# shield.net
KiCad netlist of a schematic drawn in EAGLE
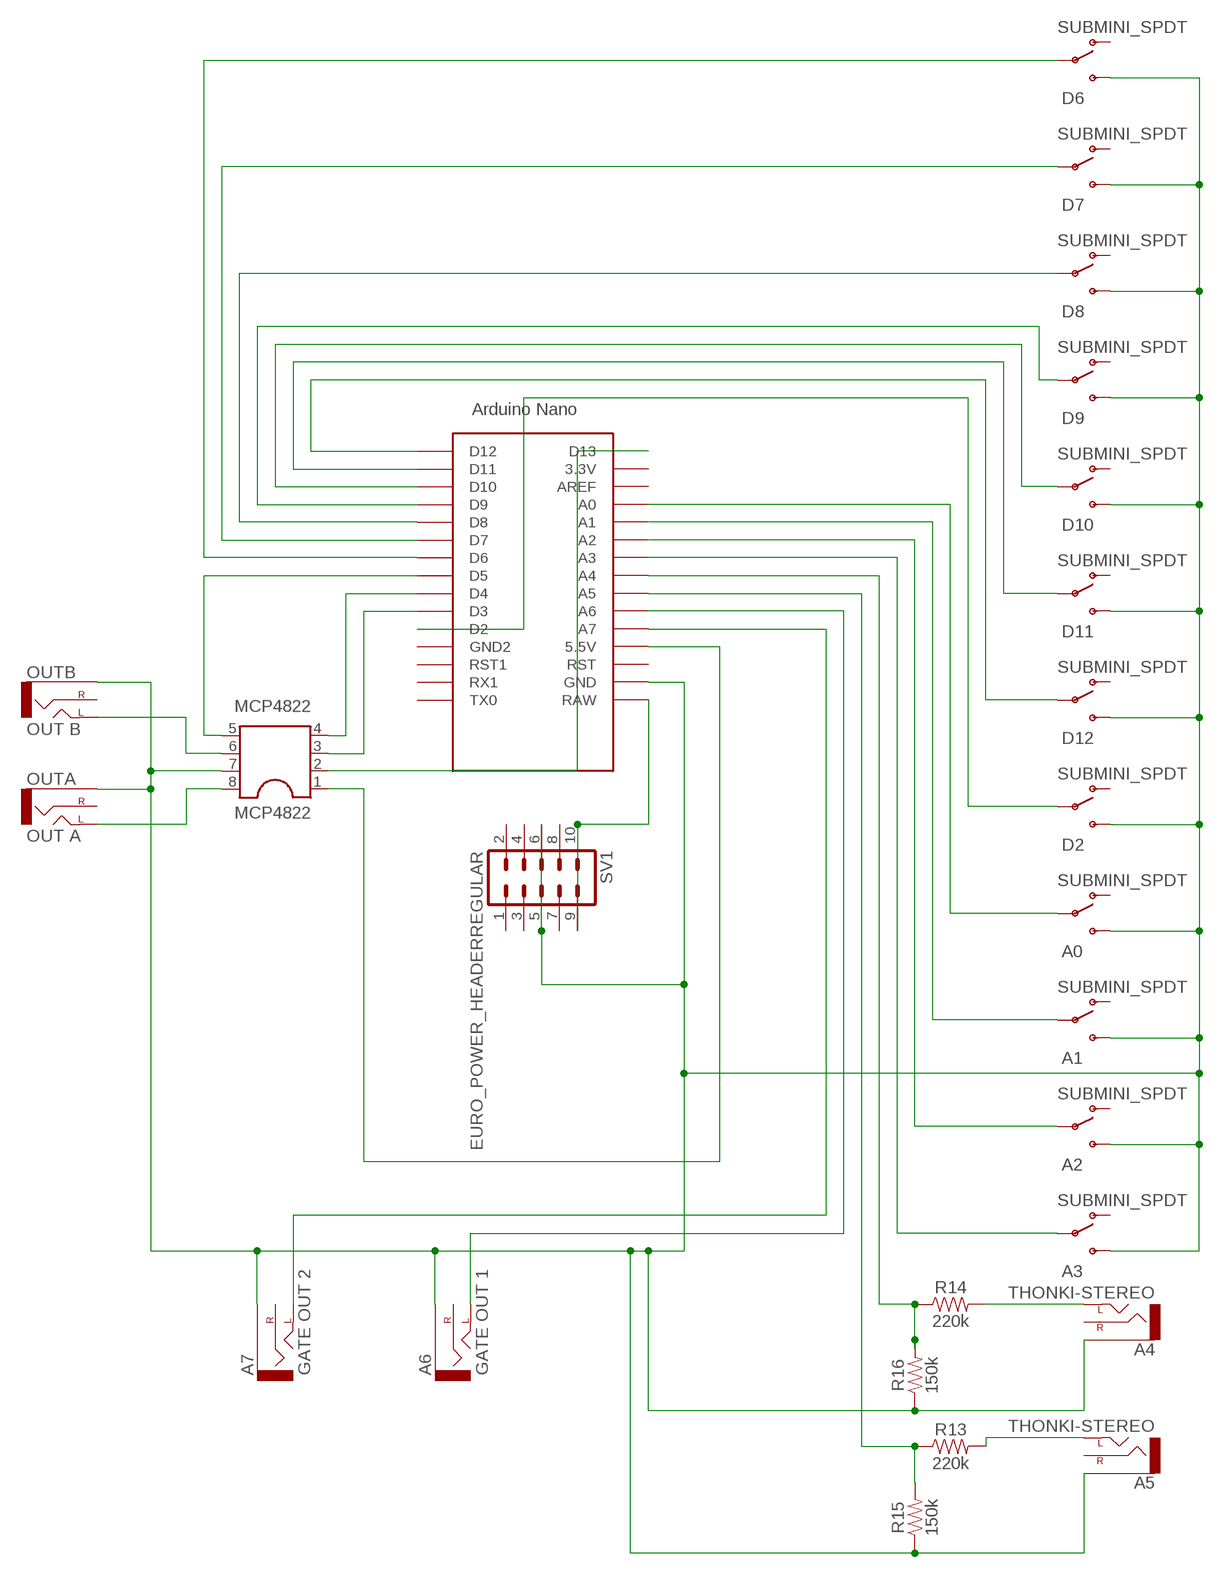
[diagram p0: schematic, sheet 1]

(export (version "E")
  (design (tool "Eeschema 10.0.6"))
  (components
    (comp (ref "A0")
      (value "SUBMINI_SPDT")
      (footprint "eagle-import:SUBMINI_TOGGLE")
      (libsource (lib "eagle-import") (part "SUBMINI_SPDT"))
    )
    (comp (ref "A1")
      (value "SUBMINI_SPDT")
      (footprint "eagle-import:SUBMINI_TOGGLE")
      (libsource (lib "eagle-import") (part "SUBMINI_SPDT"))
    )
    (comp (ref "A2")
      (value "SUBMINI_SPDT")
      (footprint "eagle-import:SUBMINI_TOGGLE")
      (libsource (lib "eagle-import") (part "SUBMINI_SPDT"))
    )
    (comp (ref "A3")
      (value "SUBMINI_SPDT")
      (footprint "eagle-import:SUBMINI_TOGGLE")
      (libsource (lib "eagle-import") (part "SUBMINI_SPDT"))
    )
    (comp (ref "A4")
      (value "THONKI-STEREO")
      (footprint "eagle-import:WQP-PJ366ST_JACK")
      (libsource (lib "eagle-import") (part "THONKI-STEREO"))
    )
    (comp (ref "A5")
      (value "THONKI-STEREO")
      (footprint "eagle-import:WQP-PJ366ST_JACK")
      (libsource (lib "eagle-import") (part "THONKI-STEREO"))
    )
    (comp (ref "A6")
      (value "GATE OUT 1")
      (footprint "eagle-import:WQP-PJ366ST_JACK")
      (libsource (lib "eagle-import") (part "THONKI-STEREO"))
    )
    (comp (ref "A7")
      (value "GATE OUT 2")
      (footprint "eagle-import:WQP-PJ366ST_JACK")
      (libsource (lib "eagle-import") (part "THONKI-STEREO"))
    )
    (comp (ref "D2")
      (value "SUBMINI_SPDT")
      (footprint "eagle-import:SUBMINI_TOGGLE")
      (libsource (lib "eagle-import") (part "SUBMINI_SPDT"))
    )
    (comp (ref "D6")
      (value "SUBMINI_SPDT")
      (footprint "eagle-import:SUBMINI_TOGGLE")
      (libsource (lib "eagle-import") (part "SUBMINI_SPDT"))
    )
    (comp (ref "D7")
      (value "SUBMINI_SPDT")
      (footprint "eagle-import:SUBMINI_TOGGLE")
      (libsource (lib "eagle-import") (part "SUBMINI_SPDT"))
    )
    (comp (ref "D8")
      (value "SUBMINI_SPDT")
      (footprint "eagle-import:SUBMINI_TOGGLE")
      (libsource (lib "eagle-import") (part "SUBMINI_SPDT"))
    )
    (comp (ref "D9")
      (value "SUBMINI_SPDT")
      (footprint "eagle-import:SUBMINI_TOGGLE")
      (libsource (lib "eagle-import") (part "SUBMINI_SPDT"))
    )
    (comp (ref "D10")
      (value "SUBMINI_SPDT")
      (footprint "eagle-import:SUBMINI_TOGGLE")
      (libsource (lib "eagle-import") (part "SUBMINI_SPDT"))
    )
    (comp (ref "D11")
      (value "SUBMINI_SPDT")
      (footprint "eagle-import:SUBMINI_TOGGLE")
      (libsource (lib "eagle-import") (part "SUBMINI_SPDT"))
    )
    (comp (ref "D12")
      (value "SUBMINI_SPDT")
      (footprint "eagle-import:SUBMINI_TOGGLE")
      (libsource (lib "eagle-import") (part "SUBMINI_SPDT"))
    )
    (comp (ref "MCP4822")
      (value "MCP4822")
      (footprint "eagle-import:DIL08")
      (libsource (lib "eagle-import") (part "DIL8"))
    )
    (comp (ref "OUTA")
      (value "OUT A")
      (footprint "eagle-import:WQP-PJ366ST_JACK")
      (libsource (lib "eagle-import") (part "THONKI-STEREO"))
    )
    (comp (ref "OUTB")
      (value "OUT B")
      (footprint "eagle-import:WQP-PJ366ST_JACK")
      (libsource (lib "eagle-import") (part "THONKI-STEREO"))
    )
    (comp (ref "R13")
      (value "220k")
      (footprint "eagle-import:AXIAL-0.3")
      (libsource (lib "eagle-import") (part "10KOHM-HORIZ-1/4W-5%"))
    )
    (comp (ref "R14")
      (value "220k")
      (footprint "eagle-import:AXIAL-0.3")
      (libsource (lib "eagle-import") (part "10KOHM-HORIZ-1/4W-5%"))
    )
    (comp (ref "R15")
      (value "150k")
      (footprint "eagle-import:AXIAL-0.3")
      (libsource (lib "eagle-import") (part "10KOHM-HORIZ-1/4W-5%"))
    )
    (comp (ref "R16")
      (value "150k")
      (footprint "eagle-import:AXIAL-0.3")
      (libsource (lib "eagle-import") (part "10KOHM-HORIZ-1/4W-5%"))
    )
    (comp (ref "SV1")
      (value "EURO_POWER_HEADERREGULAR")
      (footprint "eagle-import:EURO_POWER_HEADER")
      (libsource (lib "eagle-import") (part "EURO_POWER_HEADERREGULAR"))
    )
    (comp (ref "U$1")
      (value "NANO")
      (footprint "eagle-import:NANO")
      (libsource (lib "eagle-import") (part "NANO"))
    )
  )
  (nets
    (net (code "1") (name "Net-(A0-COMMON)") (class "Default")
      (node (ref "A0") (pin "COM") (pinfunction "COMMON_COM") (pintype "passive"))
      (node (ref "U$1") (pin "A0") (pinfunction "A0_A0") (pintype "bidirectional"))
    )
    (net (code "2") (name "Net-(A0-S)") (class "Default")
      (node (ref "A0") (pin "3") (pinfunction "S_3") (pintype "passive"))
      (node (ref "A1") (pin "3") (pinfunction "S_3") (pintype "passive"))
      (node (ref "A2") (pin "3") (pinfunction "S_3") (pintype "passive"))
      (node (ref "A3") (pin "3") (pinfunction "S_3") (pintype "passive"))
      (node (ref "A4") (pin "P$3_SLEEVE") (pinfunction "SLEEVE_P$3_SLEEVE") (pintype "bidirectional"))
      (node (ref "A5") (pin "P$3_SLEEVE") (pinfunction "SLEEVE_P$3_SLEEVE") (pintype "bidirectional"))
      (node (ref "A6") (pin "P$3_SLEEVE") (pinfunction "SLEEVE_P$3_SLEEVE") (pintype "bidirectional"))
      (node (ref "A7") (pin "P$3_SLEEVE") (pinfunction "SLEEVE_P$3_SLEEVE") (pintype "bidirectional"))
      (node (ref "D10") (pin "3") (pinfunction "S_3") (pintype "passive"))
      (node (ref "D11") (pin "3") (pinfunction "S_3") (pintype "passive"))
      (node (ref "D12") (pin "3") (pinfunction "S_3") (pintype "passive"))
      (node (ref "D2") (pin "3") (pinfunction "S_3") (pintype "passive"))
      (node (ref "D6") (pin "3") (pinfunction "S_3") (pintype "passive"))
      (node (ref "D7") (pin "3") (pinfunction "S_3") (pintype "passive"))
      (node (ref "D8") (pin "3") (pinfunction "S_3") (pintype "passive"))
      (node (ref "D9") (pin "3") (pinfunction "S_3") (pintype "passive"))
      (node (ref "MCP4822") (pin "7") (pinfunction "7_7") (pintype "passive"))
      (node (ref "OUTA") (pin "P$3_SLEEVE") (pinfunction "SLEEVE_P$3_SLEEVE") (pintype "bidirectional"))
      (node (ref "OUTB") (pin "P$3_SLEEVE") (pinfunction "SLEEVE_P$3_SLEEVE") (pintype "bidirectional"))
      (node (ref "R15") (pin "P$1") (pinfunction "1_P$1") (pintype "passive"))
      (node (ref "R16") (pin "P$1") (pinfunction "1_P$1") (pintype "passive"))
      (node (ref "SV1") (pin "5") (pinfunction "5_5") (pintype "passive"))
      (node (ref "SV1") (pin "6") (pinfunction "6_6") (pintype "passive"))
      (node (ref "U$1") (pin "GND") (pinfunction "GND_GND") (pintype "bidirectional"))
    )
    (net (code "3") (name "Net-(A1-COMMON)") (class "Default")
      (node (ref "A1") (pin "COM") (pinfunction "COMMON_COM") (pintype "passive"))
      (node (ref "U$1") (pin "A1") (pinfunction "A1_A1") (pintype "bidirectional"))
    )
    (net (code "4") (name "Net-(A2-COMMON)") (class "Default")
      (node (ref "A2") (pin "COM") (pinfunction "COMMON_COM") (pintype "passive"))
      (node (ref "U$1") (pin "A2") (pinfunction "A2_A2") (pintype "bidirectional"))
    )
    (net (code "5") (name "Net-(A3-COMMON)") (class "Default")
      (node (ref "A3") (pin "COM") (pinfunction "COMMON_COM") (pintype "passive"))
      (node (ref "U$1") (pin "A3") (pinfunction "A3_A3") (pintype "bidirectional"))
    )
    (net (code "6") (name "Net-(A4-LEFT)") (class "Default")
      (node (ref "A4") (pin "P$1_TIP") (pinfunction "LEFT_P$1_TIP") (pintype "bidirectional"))
      (node (ref "R14") (pin "P$2") (pinfunction "2_P$2") (pintype "passive"))
    )
    (net (code "7") (name "Net-(A5-LEFT)") (class "Default")
      (node (ref "A5") (pin "P$1_TIP") (pinfunction "LEFT_P$1_TIP") (pintype "bidirectional"))
      (node (ref "R13") (pin "P$2") (pinfunction "2_P$2") (pintype "passive"))
    )
    (net (code "8") (name "Net-(A6-LEFT)") (class "Default")
      (node (ref "A6") (pin "P$1_TIP") (pinfunction "LEFT_P$1_TIP") (pintype "bidirectional"))
      (node (ref "U$1") (pin "A6") (pinfunction "A6_A6") (pintype "bidirectional"))
    )
    (net (code "9") (name "Net-(A7-LEFT)") (class "Default")
      (node (ref "A7") (pin "P$1_TIP") (pinfunction "LEFT_P$1_TIP") (pintype "bidirectional"))
      (node (ref "U$1") (pin "A7") (pinfunction "A7_A7") (pintype "bidirectional"))
    )
    (net (code "10") (name "Net-(D2-COMMON)") (class "Default")
      (node (ref "D2") (pin "COM") (pinfunction "COMMON_COM") (pintype "passive"))
      (node (ref "U$1") (pin "D2") (pinfunction "D2_D2") (pintype "bidirectional"))
    )
    (net (code "11") (name "Net-(D6-COMMON)") (class "Default")
      (node (ref "D6") (pin "COM") (pinfunction "COMMON_COM") (pintype "passive"))
      (node (ref "U$1") (pin "D6") (pinfunction "D6_D6") (pintype "bidirectional"))
    )
    (net (code "12") (name "Net-(D7-COMMON)") (class "Default")
      (node (ref "D7") (pin "COM") (pinfunction "COMMON_COM") (pintype "passive"))
      (node (ref "U$1") (pin "D7") (pinfunction "D7_D7") (pintype "bidirectional"))
    )
    (net (code "13") (name "Net-(D8-COMMON)") (class "Default")
      (node (ref "D8") (pin "COM") (pinfunction "COMMON_COM") (pintype "passive"))
      (node (ref "U$1") (pin "D8") (pinfunction "D8_D8") (pintype "bidirectional"))
    )
    (net (code "14") (name "Net-(D9-COMMON)") (class "Default")
      (node (ref "D9") (pin "COM") (pinfunction "COMMON_COM") (pintype "passive"))
      (node (ref "U$1") (pin "D9") (pinfunction "D9_D9") (pintype "bidirectional"))
    )
    (net (code "15") (name "Net-(D10-COMMON)") (class "Default")
      (node (ref "D10") (pin "COM") (pinfunction "COMMON_COM") (pintype "passive"))
      (node (ref "U$1") (pin "D10") (pinfunction "D10_D10") (pintype "bidirectional"))
    )
    (net (code "16") (name "Net-(D11-COMMON)") (class "Default")
      (node (ref "D11") (pin "COM") (pinfunction "COMMON_COM") (pintype "passive"))
      (node (ref "U$1") (pin "D11") (pinfunction "D11_D11") (pintype "bidirectional"))
    )
    (net (code "17") (name "Net-(D12-COMMON)") (class "Default")
      (node (ref "D12") (pin "COM") (pinfunction "COMMON_COM") (pintype "passive"))
      (node (ref "U$1") (pin "D12") (pinfunction "D12_D12") (pintype "bidirectional"))
    )
    (net (code "18") (name "Net-(MCP4822-Pad2)") (class "Default")
      (node (ref "MCP4822") (pin "2") (pinfunction "2_2") (pintype "passive"))
      (node (ref "U$1") (pin "D13") (pinfunction "D13_D13") (pintype "bidirectional"))
    )
    (net (code "19") (name "Net-(MCP4822-Pad3)") (class "Default")
      (node (ref "MCP4822") (pin "3") (pinfunction "3_3") (pintype "passive"))
      (node (ref "U$1") (pin "D3") (pinfunction "D3_D3") (pintype "bidirectional"))
    )
    (net (code "20") (name "Net-(MCP4822-Pad4)") (class "Default")
      (node (ref "MCP4822") (pin "4") (pinfunction "4_4") (pintype "passive"))
      (node (ref "U$1") (pin "D4") (pinfunction "D4_D4") (pintype "bidirectional"))
    )
    (net (code "21") (name "Net-(MCP4822-Pad5)") (class "Default")
      (node (ref "MCP4822") (pin "5") (pinfunction "5_5") (pintype "passive"))
      (node (ref "U$1") (pin "D5") (pinfunction "D5_D5") (pintype "bidirectional"))
    )
    (net (code "22") (name "Net-(OUTA-LEFT)") (class "Default")
      (node (ref "MCP4822") (pin "8") (pinfunction "8_8") (pintype "passive"))
      (node (ref "OUTA") (pin "P$1_TIP") (pinfunction "LEFT_P$1_TIP") (pintype "bidirectional"))
    )
    (net (code "23") (name "Net-(OUTB-LEFT)") (class "Default")
      (node (ref "MCP4822") (pin "6") (pinfunction "6_6") (pintype "passive"))
      (node (ref "OUTB") (pin "P$1_TIP") (pinfunction "LEFT_P$1_TIP") (pintype "bidirectional"))
    )
    (net (code "24") (name "Net-(R13-1)") (class "Default")
      (node (ref "R13") (pin "P$1") (pinfunction "1_P$1") (pintype "passive"))
      (node (ref "R15") (pin "P$2") (pinfunction "2_P$2") (pintype "passive"))
      (node (ref "U$1") (pin "A5") (pinfunction "A5_A5") (pintype "bidirectional"))
    )
    (net (code "25") (name "Net-(R14-1)") (class "Default")
      (node (ref "R14") (pin "P$1") (pinfunction "1_P$1") (pintype "passive"))
      (node (ref "R16") (pin "P$2") (pinfunction "2_P$2") (pintype "passive"))
      (node (ref "U$1") (pin "A4") (pinfunction "A4_A4") (pintype "bidirectional"))
    )
    (net (code "26") (name "Net-(SV1-Pad10)") (class "Default")
      (node (ref "SV1") (pin "10") (pinfunction "10_10") (pintype "passive"))
      (node (ref "SV1") (pin "9") (pinfunction "9_9") (pintype "passive"))
      (node (ref "U$1") (pin "RAW") (pinfunction "RAW_RAW") (pintype "bidirectional"))
    )
    (net (code "27") (name "Net-(U$1-5.5V)") (class "Default")
      (node (ref "MCP4822") (pin "1") (pinfunction "1_1") (pintype "passive"))
      (node (ref "U$1") (pin "5V") (pinfunction "5.5V_5V") (pintype "bidirectional"))
    )
    (net (code "28") (name "unconnected-(A0-O-Pad1)") (class "Default")
      (node (ref "A0") (pin "1") (pinfunction "O_1") (pintype "passive"))
    )
    (net (code "29") (name "unconnected-(A1-O-Pad1)") (class "Default")
      (node (ref "A1") (pin "1") (pinfunction "O_1") (pintype "passive"))
    )
    (net (code "30") (name "unconnected-(A2-O-Pad1)") (class "Default")
      (node (ref "A2") (pin "1") (pinfunction "O_1") (pintype "passive"))
    )
    (net (code "31") (name "unconnected-(A3-O-Pad1)") (class "Default")
      (node (ref "A3") (pin "1") (pinfunction "O_1") (pintype "passive"))
    )
    (net (code "32") (name "unconnected-(A4-RIGHT-PadP$2_SWITCH)") (class "Default")
      (node (ref "A4") (pin "P$2_SWITCH") (pinfunction "RIGHT_P$2_SWITCH") (pintype "bidirectional"))
    )
    (net (code "33") (name "unconnected-(A5-RIGHT-PadP$2_SWITCH)") (class "Default")
      (node (ref "A5") (pin "P$2_SWITCH") (pinfunction "RIGHT_P$2_SWITCH") (pintype "bidirectional"))
    )
    (net (code "34") (name "unconnected-(A6-RIGHT-PadP$2_SWITCH)") (class "Default")
      (node (ref "A6") (pin "P$2_SWITCH") (pinfunction "RIGHT_P$2_SWITCH") (pintype "bidirectional"))
    )
    (net (code "35") (name "unconnected-(A7-RIGHT-PadP$2_SWITCH)") (class "Default")
      (node (ref "A7") (pin "P$2_SWITCH") (pinfunction "RIGHT_P$2_SWITCH") (pintype "bidirectional"))
    )
    (net (code "36") (name "unconnected-(D2-O-Pad1)") (class "Default")
      (node (ref "D2") (pin "1") (pinfunction "O_1") (pintype "passive"))
    )
    (net (code "37") (name "unconnected-(D6-O-Pad1)") (class "Default")
      (node (ref "D6") (pin "1") (pinfunction "O_1") (pintype "passive"))
    )
    (net (code "38") (name "unconnected-(D7-O-Pad1)") (class "Default")
      (node (ref "D7") (pin "1") (pinfunction "O_1") (pintype "passive"))
    )
    (net (code "39") (name "unconnected-(D8-O-Pad1)") (class "Default")
      (node (ref "D8") (pin "1") (pinfunction "O_1") (pintype "passive"))
    )
    (net (code "40") (name "unconnected-(D9-O-Pad1)") (class "Default")
      (node (ref "D9") (pin "1") (pinfunction "O_1") (pintype "passive"))
    )
    (net (code "41") (name "unconnected-(D10-O-Pad1)") (class "Default")
      (node (ref "D10") (pin "1") (pinfunction "O_1") (pintype "passive"))
    )
    (net (code "42") (name "unconnected-(D11-O-Pad1)") (class "Default")
      (node (ref "D11") (pin "1") (pinfunction "O_1") (pintype "passive"))
    )
    (net (code "43") (name "unconnected-(D12-O-Pad1)") (class "Default")
      (node (ref "D12") (pin "1") (pinfunction "O_1") (pintype "passive"))
    )
    (net (code "44") (name "unconnected-(OUTA-RIGHT-PadP$2_SWITCH)") (class "Default")
      (node (ref "OUTA") (pin "P$2_SWITCH") (pinfunction "RIGHT_P$2_SWITCH") (pintype "bidirectional"))
    )
    (net (code "45") (name "unconnected-(OUTB-RIGHT-PadP$2_SWITCH)") (class "Default")
      (node (ref "OUTB") (pin "P$2_SWITCH") (pinfunction "RIGHT_P$2_SWITCH") (pintype "bidirectional"))
    )
    (net (code "46") (name "unconnected-(SV1-Pad1)") (class "Default")
      (node (ref "SV1") (pin "1") (pinfunction "1_1") (pintype "passive"))
    )
    (net (code "47") (name "unconnected-(SV1-Pad2)") (class "Default")
      (node (ref "SV1") (pin "2") (pinfunction "2_2") (pintype "passive"))
    )
    (net (code "48") (name "unconnected-(SV1-Pad3)") (class "Default")
      (node (ref "SV1") (pin "3") (pinfunction "3_3") (pintype "passive"))
    )
    (net (code "49") (name "unconnected-(SV1-Pad4)") (class "Default")
      (node (ref "SV1") (pin "4") (pinfunction "4_4") (pintype "passive"))
    )
    (net (code "50") (name "unconnected-(SV1-Pad7)") (class "Default")
      (node (ref "SV1") (pin "7") (pinfunction "7_7") (pintype "passive"))
    )
    (net (code "51") (name "unconnected-(SV1-Pad8)") (class "Default")
      (node (ref "SV1") (pin "8") (pinfunction "8_8") (pintype "passive"))
    )
    (net (code "52") (name "unconnected-(U$1-GND2-PadGND1)") (class "Default")
      (node (ref "U$1") (pin "GND1") (pinfunction "GND2_GND1") (pintype "bidirectional"))
    )
    (net (code "53") (name "unconnected-(U$1-Pad3.3V)") (class "Default")
      (node (ref "U$1") (pin "3.3V") (pinfunction "3.3V_3.3V") (pintype "bidirectional"))
    )
    (net (code "54") (name "unconnected-(U$1-PadAREF)") (class "Default")
      (node (ref "U$1") (pin "AREF") (pinfunction "AREF_AREF") (pintype "bidirectional"))
    )
    (net (code "55") (name "unconnected-(U$1-PadICSP1)") (class "Default")
      (node (ref "U$1") (pin "ICSP1") (pinfunction "ICSP1_ICSP1") (pintype "bidirectional"))
    )
    (net (code "56") (name "unconnected-(U$1-PadICSP2)") (class "Default")
      (node (ref "U$1") (pin "ICSP2") (pinfunction "ICSP2_ICSP2") (pintype "bidirectional"))
    )
    (net (code "57") (name "unconnected-(U$1-PadICSP3)") (class "Default")
      (node (ref "U$1") (pin "ICSP3") (pinfunction "ICSP3_ICSP3") (pintype "bidirectional"))
    )
    (net (code "58") (name "unconnected-(U$1-PadICSP4)") (class "Default")
      (node (ref "U$1") (pin "ICSP4") (pinfunction "ICSP4_ICSP4") (pintype "bidirectional"))
    )
    (net (code "59") (name "unconnected-(U$1-PadICSP5)") (class "Default")
      (node (ref "U$1") (pin "ICSP5") (pinfunction "ICSP5_ICSP5") (pintype "bidirectional"))
    )
    (net (code "60") (name "unconnected-(U$1-PadICSP6)") (class "Default")
      (node (ref "U$1") (pin "ICSP6") (pinfunction "ICSP6_ICSP6") (pintype "bidirectional"))
    )
    (net (code "61") (name "unconnected-(U$1-PadRST)") (class "Default")
      (node (ref "U$1") (pin "RST") (pinfunction "RST_RST") (pintype "bidirectional"))
    )
    (net (code "62") (name "unconnected-(U$1-PadRST1)") (class "Default")
      (node (ref "U$1") (pin "RST1") (pinfunction "RST1_RST1") (pintype "bidirectional"))
    )
    (net (code "63") (name "unconnected-(U$1-PadRX1)") (class "Default")
      (node (ref "U$1") (pin "RX1") (pinfunction "RX1_RX1") (pintype "bidirectional"))
    )
    (net (code "64") (name "unconnected-(U$1-PadTX0)") (class "Default")
      (node (ref "U$1") (pin "TX0") (pinfunction "TX0_TX0") (pintype "bidirectional"))
    )
  )
)
